# MCU.net
KiCad netlist of a schematic drawn in Altium Designer
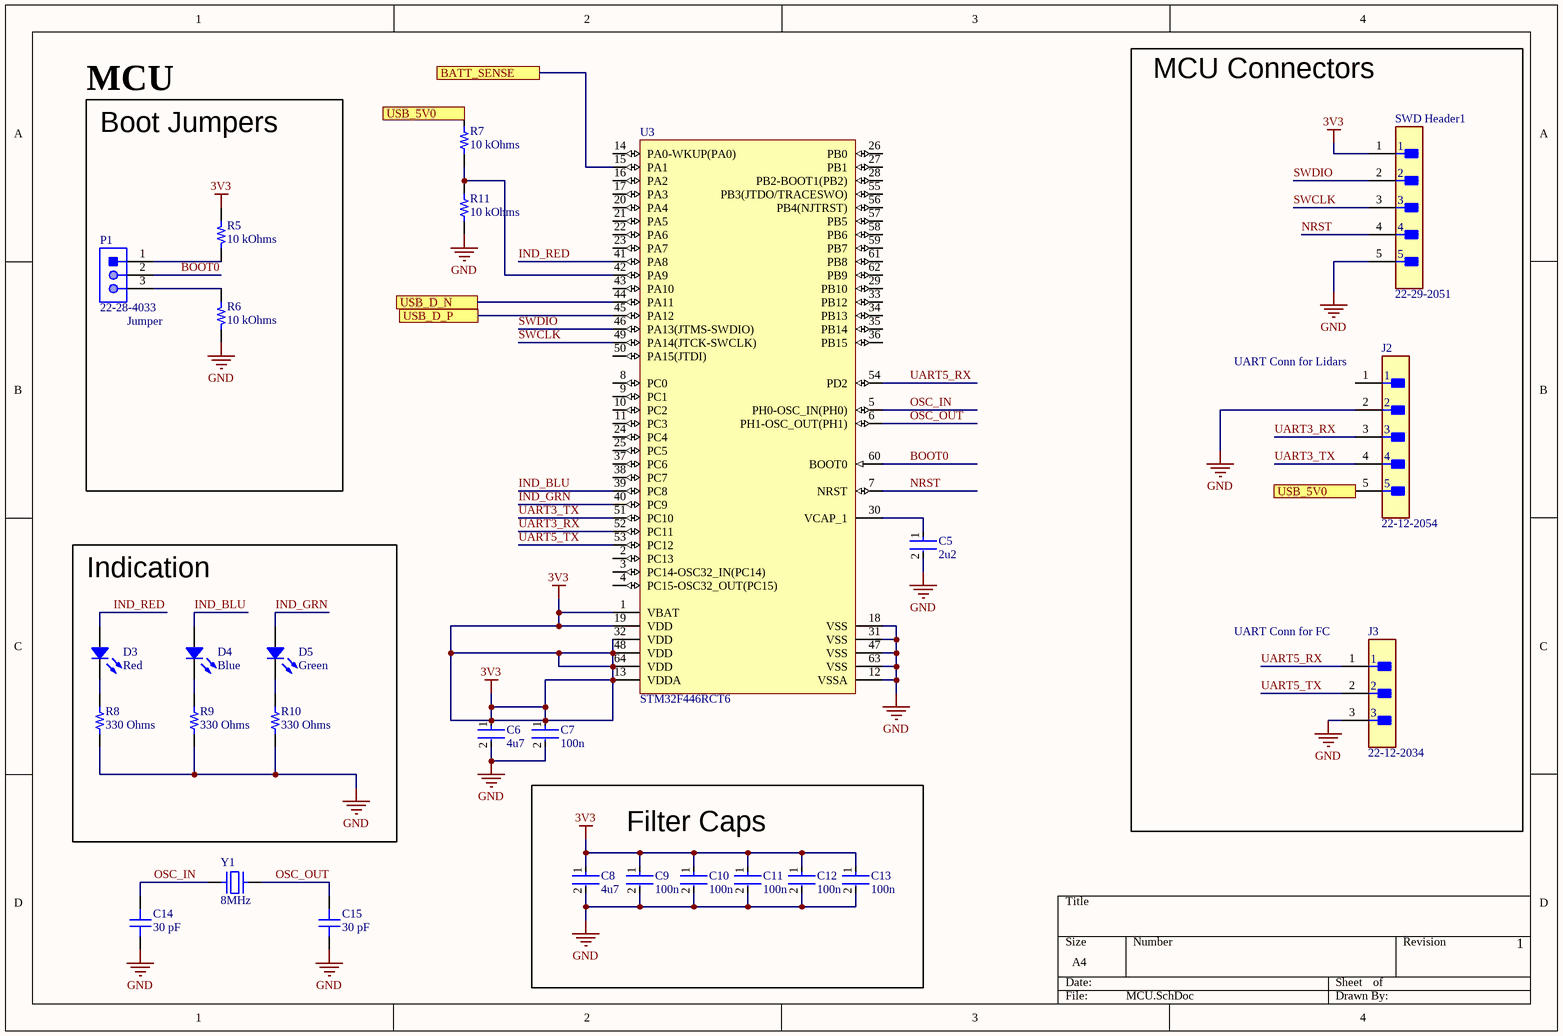
[diagram p0: MCU.SchDoc]

(export (version "E")
  (design (tool "Eeschema 10.0.6"))
  (components
    (comp (ref "C5")
      (value "2u2")
      (footprint "FP-CL10-IPC_C")
      (description "Cap Ceramic 4.7uF 10V X5R ±10% Pad SMD 0603 +85°C T/R")
      (fields (field (name "TOLERANCE") "10%"))
      (libsource (lib "Altium Content Vault") (part "b4654b650e69147ec39a6b967a45e02"))
    )
    (comp (ref "C6")
      (value "4u7")
      (footprint "FP-CL10-IPC_C")
      (description "Cap Ceramic 4.7uF 10V X5R ±10% Pad SMD 0603 +85°C T/R")
      (fields (field (name "TOLERANCE") "10%"))
      (libsource (lib "Altium Content Vault") (part "b4654b650e69147ec39a6b967a45e02"))
    )
    (comp (ref "C7")
      (value "100n")
      (footprint "FP-CL779-IPC_C")
      (description "Cap Ceramic 100nF 50V X7R ±10% SMD 0402 +125°C Paper T/R")
      (libsource (lib "Altium Content Vault") (part "b4654b650e69147ec39a6b967a45e02"))
    )
    (comp (ref "C8")
      (value "4u7")
      (footprint "FP-CL10-IPC_C")
      (description "Cap Ceramic 4.7uF 10V X5R ±10% Pad SMD 0603 +85°C T/R")
      (fields (field (name "TOLERANCE") "10%"))
      (libsource (lib "Altium Content Vault") (part "b4654b650e69147ec39a6b967a45e02"))
    )
    (comp (ref "C9")
      (value "100n")
      (footprint "FP-CL779-IPC_C")
      (description "Cap Ceramic 100nF 50V X7R ±10% SMD 0402 +125°C Paper T/R")
      (libsource (lib "Altium Content Vault") (part "b4654b650e69147ec39a6b967a45e02"))
    )
    (comp (ref "C10")
      (value "100n")
      (footprint "FP-CL779-IPC_C")
      (description "Cap Ceramic 100nF 50V X7R ±10% SMD 0402 +125°C Paper T/R")
      (libsource (lib "Altium Content Vault") (part "b4654b650e69147ec39a6b967a45e02"))
    )
    (comp (ref "C11")
      (value "100n")
      (footprint "FP-CL779-IPC_C")
      (description "Cap Ceramic 100nF 50V X7R ±10% SMD 0402 +125°C Paper T/R")
      (libsource (lib "Altium Content Vault") (part "b4654b650e69147ec39a6b967a45e02"))
    )
    (comp (ref "C12")
      (value "100n")
      (footprint "FP-CL779-IPC_C")
      (description "Cap Ceramic 100nF 50V X7R ±10% SMD 0402 +125°C Paper T/R")
      (libsource (lib "Altium Content Vault") (part "b4654b650e69147ec39a6b967a45e02"))
    )
    (comp (ref "C13")
      (value "100n")
      (footprint "FP-CL779-IPC_C")
      (description "Cap Ceramic 100nF 50V X7R ±10% SMD 0402 +125°C Paper T/R")
      (libsource (lib "Altium Content Vault") (part "b4654b650e69147ec39a6b967a45e02"))
    )
    (comp (ref "C14")
      (value "30 pF")
      (footprint "CAP 0603_1608")
      (description "CAP CER 30PF 50V C0G/NP0 0603")
      (fields
        (field (name "PART NUMBER") "0603N300J500CT")
        (field (name "MANUFACTURER") "Walsin Technology Corporation")
      )
      (libsource (lib "Celestial Altium Library - altium_library") (part "Capacitor"))
    )
    (comp (ref "C15")
      (value "30 pF")
      (footprint "CAP 0603_1608")
      (description "CAP CER 30PF 50V C0G/NP0 0603")
      (fields
        (field (name "PART NUMBER") "0603N300J500CT")
        (field (name "MANUFACTURER") "Walsin Technology Corporation")
      )
      (libsource (lib "Celestial Altium Library - altium_library") (part "Capacitor"))
    )
    (comp (ref "D3")
      (value "Red")
      (footprint "LED 0603_1608 RED")
      (description "LED RED CLEAR 2SMD")
      (fields
        (field (name "PART NUMBER") "19-213SDRC/S259/TR8")
        (field (name "MANUFACTURER") "Everlight Electronics Co Ltd")
      )
      (libsource (lib "Celestial Altium Library - altium_library") (part "LED"))
    )
    (comp (ref "D4")
      (value "Blue")
      (footprint "LED 0603_1608 BLUE")
      (description "LED BLUE CLEAR 2SMD")
      (fields
        (field (name "PART NUMBER") "19-213SUBC/S400-A5/S208-2/TR8")
        (field (name "MANUFACTURER") "Everlight Electronics Co Ltd")
      )
      (libsource (lib "Celestial Altium Library - altium_library") (part "LED"))
    )
    (comp (ref "D5")
      (value "Green")
      (footprint "LED 0603_1608 GREEN")
      (description "LED GREEN DIFFUSED 0603 SMD")
      (fields (field (name "PART NUMBER") "150060GS55040") (field (name "MANUFACTURER") "Würth Elektronik"))
      (libsource (lib "Celestial Altium Library - altium_library") (part "LED"))
    )
    (comp (ref "J2")
      (value "22-12-2054")
      (footprint "FP-22-12-2054-MFG")
      (libsource (lib "Altium Content Vault") (part "bf93c07fd2649a848d0ec8585582aab"))
    )
    (comp (ref "J3")
      (value "22-12-2034")
      (footprint "FP-22-12-2034-MFG")
      (description "CONN HEADER R/A 3POS 2.54MM")
      (libsource (lib "Altium Content Vault") (part "0d3f023dd272f625e17a2be33dea85f"))
    )
    (comp (ref "P1")
      (value "22-28-4033")
      (footprint "MOLX-22-28-4033_V")
      (description "Male Header, Pitch 2.54 mm, 1 x 3 Position, Height 8.38 mm, Tail Length 3.18 mm, RoHS, Bulk")
      (fields (field (name "MANUFACTURER") "Molex"))
      (libsource (lib "Altium Content Vault") (part "CN-1P-M-R3"))
    )
    (comp (ref "R5")
      (value "10 kOhms")
      (footprint "RES 0603_1608")
      (description "P2TC0603 2PPM/C 10K 0,01% N TA")
      (fields
        (field (name "PART NUMBER") "P2TC0603D1002LNTA")
        (field (name "MANUFACTURER") "Vishay Sfernice")
      )
      (libsource (lib "Celestial Altium Library - altium_library") (part "Resistor"))
    )
    (comp (ref "R6")
      (value "10 kOhms")
      (footprint "RES 0603_1608")
      (description "P2TC0603 2PPM/C 10K 0,01% N TA")
      (fields
        (field (name "PART NUMBER") "P2TC0603D1002LNTA")
        (field (name "MANUFACTURER") "Vishay Sfernice")
      )
      (libsource (lib "Celestial Altium Library - altium_library") (part "Resistor"))
    )
    (comp (ref "R7")
      (value "10 kOhms")
      (footprint "RES 0603_1608")
      (description "1/16 WATTS PRECISION CHIP 10 KIL")
      (fields (field (name "PART NUMBER") "APC0603B10K0N") (field (name "MANUFACTURER") "Ohmite"))
      (libsource (lib "Celestial Altium Library - altium_library") (part "Resistor"))
    )
    (comp (ref "R8")
      (value "330 Ohms")
      (footprint "RES 0603_1608")
      (description "RCC0603 100 330R 1% ET1 E3")
      (fields (field (name "PART NUMBER") "RCC0603330RFKEA") (field (name "MANUFACTURER") "Vishay Dale"))
      (libsource (lib "Celestial Altium Library - altium_library") (part "Resistor"))
    )
    (comp (ref "R9")
      (value "330 Ohms")
      (footprint "RES 0603_1608")
      (description "RCC0603 100 330R 1% ET1 E3")
      (fields (field (name "PART NUMBER") "RCC0603330RFKEA") (field (name "MANUFACTURER") "Vishay Dale"))
      (libsource (lib "Celestial Altium Library - altium_library") (part "Resistor"))
    )
    (comp (ref "R10")
      (value "330 Ohms")
      (footprint "RES 0603_1608")
      (description "RCC0603 100 330R 1% ET1 E3")
      (fields (field (name "PART NUMBER") "RCC0603330RFKEA") (field (name "MANUFACTURER") "Vishay Dale"))
      (libsource (lib "Celestial Altium Library - altium_library") (part "Resistor"))
    )
    (comp (ref "R11")
      (value "10 kOhms")
      (footprint "RES 0603_1608")
      (description "1/16 WATTS PRECISION CHIP 10 KIL")
      (fields (field (name "PART NUMBER") "APC0603B10K0N") (field (name "MANUFACTURER") "Ohmite"))
      (libsource (lib "Celestial Altium Library - altium_library") (part "Resistor"))
    )
    (comp (ref "SWD Header1")
      (value "22-29-2051")
      (footprint "FP-22-29-2051-MFG")
      (description "2.54MM KK HDR VT FRICLK VRA .5AU")
      (libsource (lib "Altium Content Vault") (part "bf93c07fd2649a848d0ec8585582aab"))
    )
    (comp (ref "U3")
      (value "STM32F446RCT6")
      (footprint "STM-LQFP64_L")
      (libsource (lib "Altium Content Vault") (part "MC-ARM-STM32F446-LQFP64"))
    )
    (comp (ref "Y1")
      (value "8MHz")
      (footprint "TXC 9C")
      (description "CRYSTAL 8.0000MHZ 20PF SMD")
      (fields (field (name "PART NUMBER") "9C-8.000MBBK-T") (field (name "MANUFACTURER") "TXC CORPORATION"))
      (libsource (lib "Celestial Altium Library - altium_library") (part "TXC Crystal 9C"))
    )
  )
  (nets
    (net (code "1") (name "/BATT_SENSE") (class "Default")
      (node (ref "U3") (pin "15") (pinfunction "PA1_15") (pintype "bidirectional"))
    )
    (net (code "2") (name "/BOOT0") (class "Default")
      (node (ref "P1") (pin "2") (pinfunction "2_2") (pintype "passive"))
      (node (ref "U3") (pin "60") (pinfunction "BOOT0_60") (pintype "input"))
    )
    (net (code "3") (name "/IND_BLU") (class "Default")
      (node (ref "D4") (pin "1") (pinfunction "1_1") (pintype "passive"))
      (node (ref "U3") (pin "39") (pinfunction "PC8_39") (pintype "bidirectional"))
    )
    (net (code "4") (name "/IND_GRN") (class "Default")
      (node (ref "D5") (pin "1") (pinfunction "1_1") (pintype "passive"))
      (node (ref "U3") (pin "40") (pinfunction "PC9_40") (pintype "bidirectional"))
    )
    (net (code "5") (name "/IND_RED") (class "Default")
      (node (ref "D3") (pin "1") (pinfunction "1_1") (pintype "passive"))
      (node (ref "U3") (pin "41") (pinfunction "PA8_41") (pintype "bidirectional"))
    )
    (net (code "6") (name "/NRST") (class "Default")
      (node (ref "SWD Header1") (pin "4") (pinfunction "4_4") (pintype "passive"))
      (node (ref "U3") (pin "7") (pinfunction "NRST_7") (pintype "bidirectional"))
    )
    (net (code "7") (name "/OSC_IN") (class "Default")
      (node (ref "C14") (pin "2") (pinfunction "2_2") (pintype "passive"))
      (node (ref "U3") (pin "5") (pinfunction "PH0-OSC_IN(PH0)_5") (pintype "bidirectional"))
      (node (ref "Y1") (pin "1") (pinfunction "1_1") (pintype "passive"))
    )
    (net (code "8") (name "/OSC_OUT") (class "Default")
      (node (ref "C15") (pin "2") (pinfunction "2_2") (pintype "passive"))
      (node (ref "U3") (pin "6") (pinfunction "PH1-OSC_OUT(PH1)_6") (pintype "bidirectional"))
      (node (ref "Y1") (pin "2") (pinfunction "2_2") (pintype "passive"))
    )
    (net (code "9") (name "/SWCLK") (class "Default")
      (node (ref "SWD Header1") (pin "3") (pinfunction "3_3") (pintype "passive"))
      (node (ref "U3") (pin "49") (pinfunction "PA14(JTCK-SWCLK)_49") (pintype "bidirectional"))
    )
    (net (code "10") (name "/SWDIO") (class "Default")
      (node (ref "SWD Header1") (pin "2") (pinfunction "2_2") (pintype "passive"))
      (node (ref "U3") (pin "46") (pinfunction "PA13(JTMS-SWDIO)_46") (pintype "bidirectional"))
    )
    (net (code "11") (name "/UART3_RX") (class "Default")
      (node (ref "J2") (pin "3") (pinfunction "3_3") (pintype "passive"))
      (node (ref "U3") (pin "52") (pinfunction "PC11_52") (pintype "bidirectional"))
    )
    (net (code "12") (name "/UART3_TX") (class "Default")
      (node (ref "J2") (pin "4") (pinfunction "4_4") (pintype "passive"))
      (node (ref "U3") (pin "51") (pinfunction "PC10_51") (pintype "bidirectional"))
    )
    (net (code "13") (name "/UART5_RX") (class "Default")
      (node (ref "J3") (pin "1") (pinfunction "1_1") (pintype "passive"))
      (node (ref "U3") (pin "54") (pinfunction "PD2_54") (pintype "bidirectional"))
    )
    (net (code "14") (name "/UART5_TX") (class "Default")
      (node (ref "J3") (pin "2") (pinfunction "2_2") (pintype "passive"))
      (node (ref "U3") (pin "53") (pinfunction "PC12_53") (pintype "bidirectional"))
    )
    (net (code "15") (name "/USB_5V0") (class "Default")
      (node (ref "J2") (pin "5") (pinfunction "5_5") (pintype "passive"))
      (node (ref "R7") (pin "2") (pinfunction "2_2") (pintype "passive"))
    )
    (net (code "16") (name "/USB_D_N") (class "Default")
      (node (ref "U3") (pin "44") (pinfunction "PA11_44") (pintype "bidirectional"))
    )
    (net (code "17") (name "/USB_D_P") (class "Default")
      (node (ref "U3") (pin "45") (pinfunction "PA12_45") (pintype "bidirectional"))
    )
    (net (code "18") (name "3V3") (class "Default")
      (node (ref "C10") (pin "1") (pinfunction "1_1") (pintype "passive"))
      (node (ref "C11") (pin "1") (pinfunction "1_1") (pintype "passive"))
      (node (ref "C12") (pin "1") (pinfunction "1_1") (pintype "passive"))
      (node (ref "C13") (pin "1") (pinfunction "1_1") (pintype "passive"))
      (node (ref "C6") (pin "1") (pinfunction "1_1") (pintype "passive"))
      (node (ref "C7") (pin "1") (pinfunction "1_1") (pintype "passive"))
      (node (ref "C8") (pin "1") (pinfunction "1_1") (pintype "passive"))
      (node (ref "C9") (pin "1") (pinfunction "1_1") (pintype "passive"))
      (node (ref "R5") (pin "1") (pinfunction "1_1") (pintype "passive"))
      (node (ref "SWD Header1") (pin "1") (pinfunction "1_1") (pintype "passive"))
      (node (ref "U3") (pin "1") (pinfunction "VBAT_1") (pintype "power_in"))
      (node (ref "U3") (pin "13") (pinfunction "VDDA_13") (pintype "power_in"))
      (node (ref "U3") (pin "19") (pinfunction "VDD_19") (pintype "power_in"))
      (node (ref "U3") (pin "32") (pinfunction "VDD_32") (pintype "power_in"))
      (node (ref "U3") (pin "48") (pinfunction "VDD_48") (pintype "power_in"))
      (node (ref "U3") (pin "64") (pinfunction "VDD_64") (pintype "power_in"))
    )
    (net (code "19") (name "GND") (class "Default")
      (node (ref "C10") (pin "2") (pinfunction "2_2") (pintype "passive"))
      (node (ref "C11") (pin "2") (pinfunction "2_2") (pintype "passive"))
      (node (ref "C12") (pin "2") (pinfunction "2_2") (pintype "passive"))
      (node (ref "C13") (pin "2") (pinfunction "2_2") (pintype "passive"))
      (node (ref "C14") (pin "1") (pinfunction "1_1") (pintype "passive"))
      (node (ref "C15") (pin "1") (pinfunction "1_1") (pintype "passive"))
      (node (ref "C5") (pin "2") (pinfunction "2_2") (pintype "passive"))
      (node (ref "C6") (pin "2") (pinfunction "2_2") (pintype "passive"))
      (node (ref "C7") (pin "2") (pinfunction "2_2") (pintype "passive"))
      (node (ref "C8") (pin "2") (pinfunction "2_2") (pintype "passive"))
      (node (ref "C9") (pin "2") (pinfunction "2_2") (pintype "passive"))
      (node (ref "J2") (pin "2") (pinfunction "2_2") (pintype "passive"))
      (node (ref "J3") (pin "3") (pinfunction "3_3") (pintype "passive"))
      (node (ref "R10") (pin "1") (pinfunction "1_1") (pintype "passive"))
      (node (ref "R11") (pin "1") (pinfunction "1_1") (pintype "passive"))
      (node (ref "R6") (pin "1") (pinfunction "1_1") (pintype "passive"))
      (node (ref "R8") (pin "1") (pinfunction "1_1") (pintype "passive"))
      (node (ref "R9") (pin "1") (pinfunction "1_1") (pintype "passive"))
      (node (ref "SWD Header1") (pin "5") (pinfunction "5_5") (pintype "passive"))
      (node (ref "U3") (pin "12") (pinfunction "VSSA_12") (pintype "power_in"))
      (node (ref "U3") (pin "18") (pinfunction "VSS_18") (pintype "power_in"))
      (node (ref "U3") (pin "31") (pinfunction "VSS_31") (pintype "power_in"))
      (node (ref "U3") (pin "47") (pinfunction "VSS_47") (pintype "power_in"))
      (node (ref "U3") (pin "63") (pinfunction "VSS_63") (pintype "power_in"))
    )
    (net (code "20") (name "Net-(D3-Pad2)") (class "Default")
      (node (ref "D3") (pin "2") (pinfunction "2_2") (pintype "passive"))
      (node (ref "R8") (pin "2") (pinfunction "2_2") (pintype "passive"))
    )
    (net (code "21") (name "Net-(D4-Pad2)") (class "Default")
      (node (ref "D4") (pin "2") (pinfunction "2_2") (pintype "passive"))
      (node (ref "R9") (pin "2") (pinfunction "2_2") (pintype "passive"))
    )
    (net (code "22") (name "Net-(D5-Pad2)") (class "Default")
      (node (ref "D5") (pin "2") (pinfunction "2_2") (pintype "passive"))
      (node (ref "R10") (pin "2") (pinfunction "2_2") (pintype "passive"))
    )
    (net (code "23") (name "Net-(P1-Pad1)") (class "Default")
      (node (ref "P1") (pin "1") (pinfunction "1_1") (pintype "passive"))
      (node (ref "R5") (pin "2") (pinfunction "2_2") (pintype "passive"))
    )
    (net (code "24") (name "Net-(P1-Pad3)") (class "Default")
      (node (ref "P1") (pin "3") (pinfunction "3_3") (pintype "passive"))
      (node (ref "R6") (pin "2") (pinfunction "2_2") (pintype "passive"))
    )
    (net (code "25") (name "Net-(U3-PA9)") (class "Default")
      (node (ref "R11") (pin "2") (pinfunction "2_2") (pintype "passive"))
      (node (ref "R7") (pin "1") (pinfunction "1_1") (pintype "passive"))
      (node (ref "U3") (pin "42") (pinfunction "PA9_42") (pintype "bidirectional"))
    )
    (net (code "26") (name "Net-(U3-VCAP_1)") (class "Default")
      (node (ref "C5") (pin "1") (pinfunction "1_1") (pintype "passive"))
      (node (ref "U3") (pin "30") (pinfunction "VCAP_1_30") (pintype "passive"))
    )
    (net (code "27") (name "unconnected-(J2-Pad1)") (class "Default")
      (node (ref "J2") (pin "1") (pinfunction "1_1") (pintype "passive"))
    )
    (net (code "28") (name "unconnected-(U3-PA0-WKUP(PA0)-Pad14)") (class "Default")
      (node (ref "U3") (pin "14") (pinfunction "PA0-WKUP(PA0)_14") (pintype "bidirectional"))
    )
    (net (code "29") (name "unconnected-(U3-PA2-Pad16)") (class "Default")
      (node (ref "U3") (pin "16") (pinfunction "PA2_16") (pintype "bidirectional"))
    )
    (net (code "30") (name "unconnected-(U3-PA3-Pad17)") (class "Default")
      (node (ref "U3") (pin "17") (pinfunction "PA3_17") (pintype "bidirectional"))
    )
    (net (code "31") (name "unconnected-(U3-PA4-Pad20)") (class "Default")
      (node (ref "U3") (pin "20") (pinfunction "PA4_20") (pintype "bidirectional"))
    )
    (net (code "32") (name "unconnected-(U3-PA5-Pad21)") (class "Default")
      (node (ref "U3") (pin "21") (pinfunction "PA5_21") (pintype "bidirectional"))
    )
    (net (code "33") (name "unconnected-(U3-PA6-Pad22)") (class "Default")
      (node (ref "U3") (pin "22") (pinfunction "PA6_22") (pintype "bidirectional"))
    )
    (net (code "34") (name "unconnected-(U3-PA7-Pad23)") (class "Default")
      (node (ref "U3") (pin "23") (pinfunction "PA7_23") (pintype "bidirectional"))
    )
    (net (code "35") (name "unconnected-(U3-PA10-Pad43)") (class "Default")
      (node (ref "U3") (pin "43") (pinfunction "PA10_43") (pintype "bidirectional"))
    )
    (net (code "36") (name "unconnected-(U3-PA15(JTDI)-Pad50)") (class "Default")
      (node (ref "U3") (pin "50") (pinfunction "PA15(JTDI)_50") (pintype "bidirectional"))
    )
    (net (code "37") (name "unconnected-(U3-PB0-Pad26)") (class "Default")
      (node (ref "U3") (pin "26") (pinfunction "PB0_26") (pintype "bidirectional"))
    )
    (net (code "38") (name "unconnected-(U3-PB1-Pad27)") (class "Default")
      (node (ref "U3") (pin "27") (pinfunction "PB1_27") (pintype "bidirectional"))
    )
    (net (code "39") (name "unconnected-(U3-PB2-BOOT1(PB2)-Pad28)") (class "Default")
      (node (ref "U3") (pin "28") (pinfunction "PB2-BOOT1(PB2)_28") (pintype "bidirectional"))
    )
    (net (code "40") (name "unconnected-(U3-PB3(JTDO{slash}TRACESWO)-Pad55)") (class "Default")
      (node (ref "U3") (pin "55") (pinfunction "PB3(JTDO/TRACESWO)_55") (pintype "bidirectional"))
    )
    (net (code "41") (name "unconnected-(U3-PB4(NJTRST)-Pad56)") (class "Default")
      (node (ref "U3") (pin "56") (pinfunction "PB4(NJTRST)_56") (pintype "bidirectional"))
    )
    (net (code "42") (name "unconnected-(U3-PB5-Pad57)") (class "Default")
      (node (ref "U3") (pin "57") (pinfunction "PB5_57") (pintype "bidirectional"))
    )
    (net (code "43") (name "unconnected-(U3-PB6-Pad58)") (class "Default")
      (node (ref "U3") (pin "58") (pinfunction "PB6_58") (pintype "bidirectional"))
    )
    (net (code "44") (name "unconnected-(U3-PB7-Pad59)") (class "Default")
      (node (ref "U3") (pin "59") (pinfunction "PB7_59") (pintype "bidirectional"))
    )
    (net (code "45") (name "unconnected-(U3-PB8-Pad61)") (class "Default")
      (node (ref "U3") (pin "61") (pinfunction "PB8_61") (pintype "bidirectional"))
    )
    (net (code "46") (name "unconnected-(U3-PB9-Pad62)") (class "Default")
      (node (ref "U3") (pin "62") (pinfunction "PB9_62") (pintype "bidirectional"))
    )
    (net (code "47") (name "unconnected-(U3-PB10-Pad29)") (class "Default")
      (node (ref "U3") (pin "29") (pinfunction "PB10_29") (pintype "bidirectional"))
    )
    (net (code "48") (name "unconnected-(U3-PB12-Pad33)") (class "Default")
      (node (ref "U3") (pin "33") (pinfunction "PB12_33") (pintype "bidirectional"))
    )
    (net (code "49") (name "unconnected-(U3-PB13-Pad34)") (class "Default")
      (node (ref "U3") (pin "34") (pinfunction "PB13_34") (pintype "bidirectional"))
    )
    (net (code "50") (name "unconnected-(U3-PB14-Pad35)") (class "Default")
      (node (ref "U3") (pin "35") (pinfunction "PB14_35") (pintype "bidirectional"))
    )
    (net (code "51") (name "unconnected-(U3-PB15-Pad36)") (class "Default")
      (node (ref "U3") (pin "36") (pinfunction "PB15_36") (pintype "bidirectional"))
    )
    (net (code "52") (name "unconnected-(U3-PC0-Pad8)") (class "Default")
      (node (ref "U3") (pin "8") (pinfunction "PC0_8") (pintype "bidirectional"))
    )
    (net (code "53") (name "unconnected-(U3-PC1-Pad9)") (class "Default")
      (node (ref "U3") (pin "9") (pinfunction "PC1_9") (pintype "bidirectional"))
    )
    (net (code "54") (name "unconnected-(U3-PC2-Pad10)") (class "Default")
      (node (ref "U3") (pin "10") (pinfunction "PC2_10") (pintype "bidirectional"))
    )
    (net (code "55") (name "unconnected-(U3-PC3-Pad11)") (class "Default")
      (node (ref "U3") (pin "11") (pinfunction "PC3_11") (pintype "bidirectional"))
    )
    (net (code "56") (name "unconnected-(U3-PC4-Pad24)") (class "Default")
      (node (ref "U3") (pin "24") (pinfunction "PC4_24") (pintype "bidirectional"))
    )
    (net (code "57") (name "unconnected-(U3-PC5-Pad25)") (class "Default")
      (node (ref "U3") (pin "25") (pinfunction "PC5_25") (pintype "bidirectional"))
    )
    (net (code "58") (name "unconnected-(U3-PC6-Pad37)") (class "Default")
      (node (ref "U3") (pin "37") (pinfunction "PC6_37") (pintype "bidirectional"))
    )
    (net (code "59") (name "unconnected-(U3-PC7-Pad38)") (class "Default")
      (node (ref "U3") (pin "38") (pinfunction "PC7_38") (pintype "bidirectional"))
    )
    (net (code "60") (name "unconnected-(U3-PC13-Pad2)") (class "Default")
      (node (ref "U3") (pin "2") (pinfunction "PC13_2") (pintype "bidirectional"))
    )
    (net (code "61") (name "unconnected-(U3-PC14-OSC32_IN(PC14)-Pad3)") (class "Default")
      (node (ref "U3") (pin "3") (pinfunction "PC14-OSC32_IN(PC14)_3") (pintype "bidirectional"))
    )
    (net (code "62") (name "unconnected-(U3-PC15-OSC32_OUT(PC15)-Pad4)") (class "Default")
      (node (ref "U3") (pin "4") (pinfunction "PC15-OSC32_OUT(PC15)_4") (pintype "bidirectional"))
    )
  )
)
